# Master_MicroController.net
KiCad netlist of a schematic drawn in Altium Designer
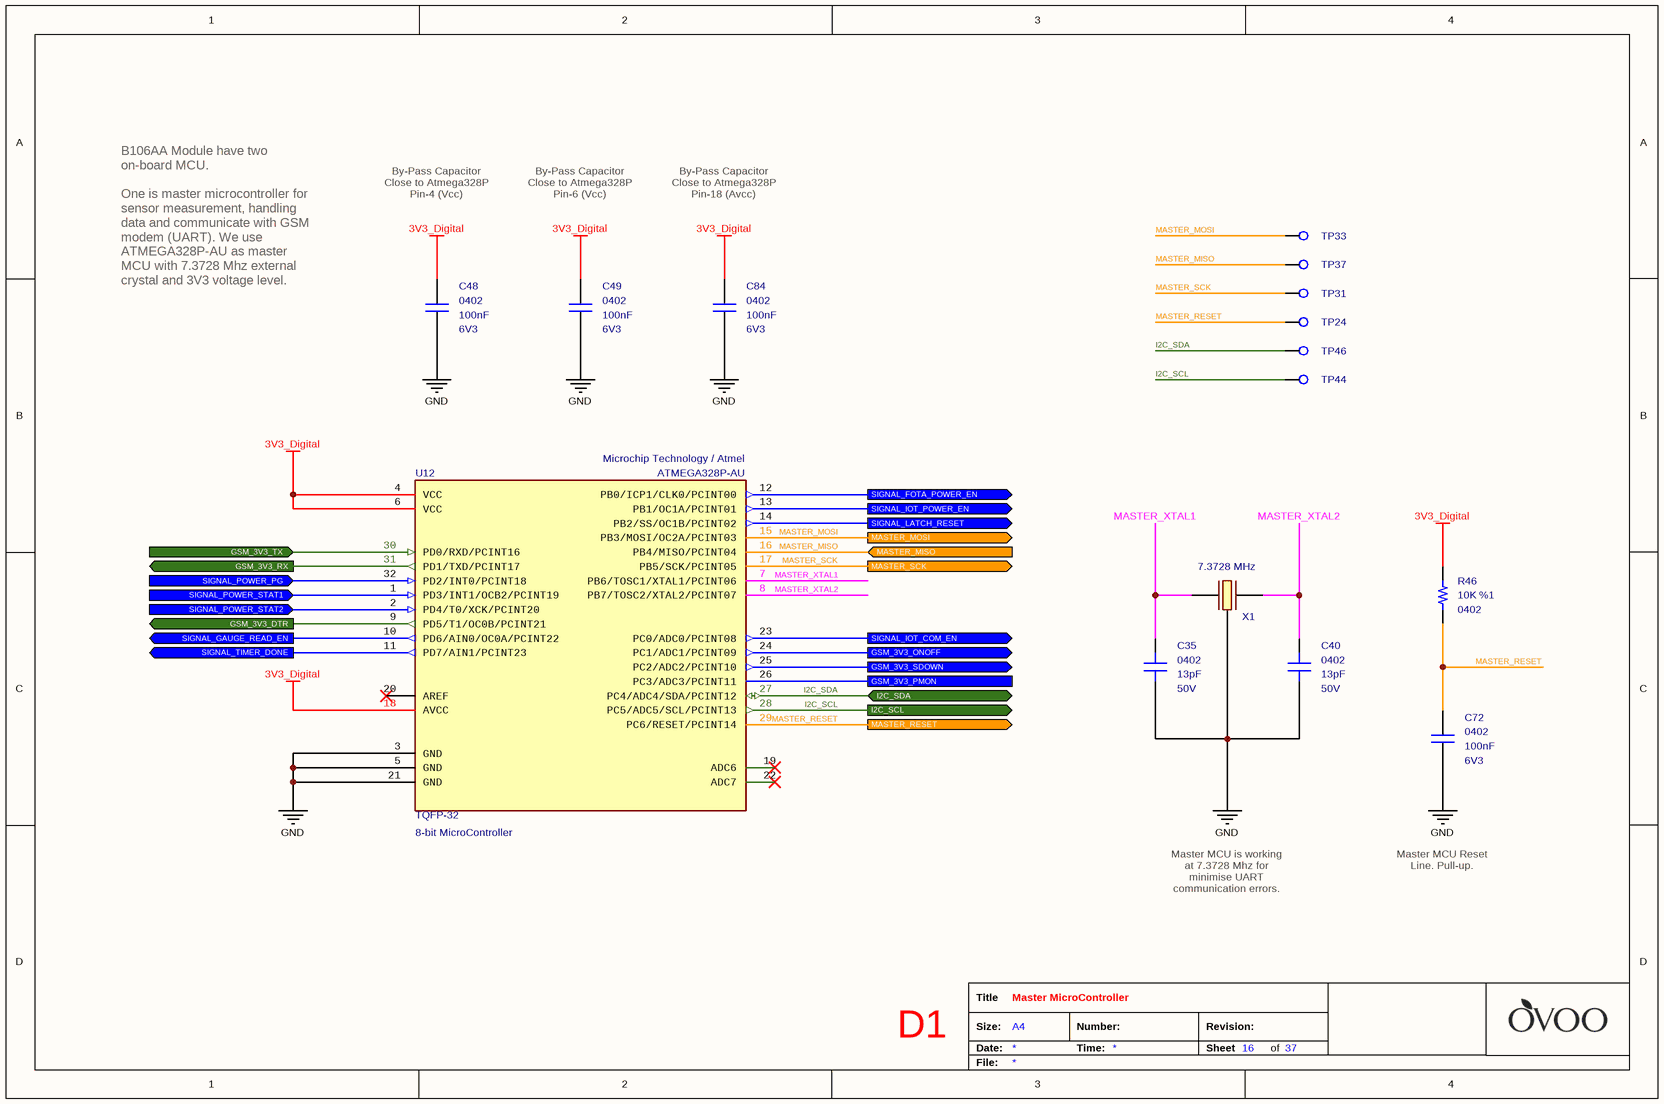
[diagram p0: Master MicroController.SchDoc]

(export (version "E")
  (design (tool "Eeschema 10.0.6"))
  (components
    (comp (ref "C35")
      (value "13pF")
      (footprint "CAPACITOR_0402")
      (description "Capacitor - 13pF [0402] (Ceramic)")
      (fields
        (field (name "MANUFACTURER_PART_NUMBER") "CBR04C130F5GAC")
        (field (name "MOUSER_PART_NUMBER") "80-CBR04C130F5GAC")
        (field (name "VOLTAGE") "50V")
        (field (name "CASE") "0402")
      )
      (libsource (lib "Ovoo_Schematic") (part "Capacitor - 13pF [0402-50V)"))
    )
    (comp (ref "C40")
      (value "13pF")
      (footprint "CAPACITOR_0402")
      (description "Capacitor - 13pF [0402] (Ceramic)")
      (fields
        (field (name "MANUFACTURER_PART_NUMBER") "CBR04C130F5GAC")
        (field (name "MOUSER_PART_NUMBER") "80-CBR04C130F5GAC")
        (field (name "VOLTAGE") "50V")
        (field (name "CASE") "0402")
      )
      (libsource (lib "Ovoo_Schematic") (part "Capacitor - 13pF [0402-50V)"))
    )
    (comp (ref "C48")
      (value "100nF")
      (footprint "CAPACITOR_0402")
      (description "Capacitor - 100nF [0402-6V3] (Ceramic)")
      (fields
        (field (name "MANUFACTURER_PART_NUMBER") "04026D104KAT4A")
        (field (name "MOUSER_PART_NUMBER") "581-04026D104KAT4A")
        (field (name "CASE") "0402")
        (field (name "VOLTAGE") "6V3")
      )
      (libsource (lib "Ovoo_Schematic") (part "Capacitor - 100nF [0402-6V3]"))
    )
    (comp (ref "C49")
      (value "100nF")
      (footprint "CAPACITOR_0402")
      (description "Capacitor - 100nF [0402-6V3] (Ceramic)")
      (fields
        (field (name "MANUFACTURER_PART_NUMBER") "04026D104KAT4A")
        (field (name "MOUSER_PART_NUMBER") "581-04026D104KAT4A")
        (field (name "CASE") "0402")
        (field (name "VOLTAGE") "6V3")
      )
      (libsource (lib "Ovoo_Schematic") (part "Capacitor - 100nF [0402-6V3]"))
    )
    (comp (ref "C72")
      (value "100nF")
      (footprint "CAPACITOR_0402")
      (description "Capacitor - 100nF [0402-6V3] (Ceramic)")
      (fields
        (field (name "MANUFACTURER_PART_NUMBER") "04026D104KAT4A")
        (field (name "MOUSER_PART_NUMBER") "581-04026D104KAT4A")
        (field (name "CASE") "0402")
        (field (name "VOLTAGE") "6V3")
      )
      (libsource (lib "Ovoo_Schematic") (part "Capacitor - 100nF [0402-6V3]"))
    )
    (comp (ref "C84")
      (value "100nF")
      (footprint "CAPACITOR_0402")
      (description "Capacitor - 100nF [0402-6V3] (Ceramic)")
      (fields
        (field (name "MANUFACTURER_PART_NUMBER") "04026D104KAT4A")
        (field (name "MOUSER_PART_NUMBER") "581-04026D104KAT4A")
        (field (name "CASE") "0402")
        (field (name "VOLTAGE") "6V3")
      )
      (libsource (lib "Ovoo_Schematic") (part "Capacitor - 100nF [0402-6V3]"))
    )
    (comp (ref "R46")
      (value "10K")
      (footprint "RESISTOR_0402")
      (description "Thick Film Resistors - SMD 1/16 W 10 Kohms 1%")
      (fields
        (field (name "MANUFACTURER_PART_NUMBER") "CRCW040210K0FKED")
        (field (name "MOUSER_PART_NUMBER") "71-CRCW0402-10K-E3")
        (field (name "TOLERANCE") "%1")
        (field (name "CASE") "0402")
      )
      (libsource (lib "Ovoo_Schematic") (part "Resistor - 10K"))
    )
    (comp (ref "TP24")
      (value "PCB - Test Point")
      (footprint "Test_Pad - Hole")
      (description "Test Point")
      (libsource (lib "Ovoo_Schematic") (part "PCB - Test Point"))
    )
    (comp (ref "TP31")
      (value "PCB - Test Point")
      (footprint "Test_Pad - Hole")
      (description "Test Point")
      (libsource (lib "Ovoo_Schematic") (part "PCB - Test Point"))
    )
    (comp (ref "TP33")
      (value "PCB - Test Point")
      (footprint "Test_Pad - Hole")
      (description "Test Point")
      (libsource (lib "Ovoo_Schematic") (part "PCB - Test Point"))
    )
    (comp (ref "TP37")
      (value "PCB - Test Point")
      (footprint "Test_Pad - Hole")
      (description "Test Point")
      (libsource (lib "Ovoo_Schematic") (part "PCB - Test Point"))
    )
    (comp (ref "TP44")
      (value "PCB - Test Point")
      (footprint "Test_Pad - Hole")
      (description "Test Point")
      (libsource (lib "Ovoo_Schematic") (part "PCB - Test Point"))
    )
    (comp (ref "TP46")
      (value "PCB - Test Point")
      (footprint "Test_Pad - Hole")
      (description "Test Point")
      (libsource (lib "Ovoo_Schematic") (part "PCB - Test Point"))
    )
    (comp (ref "U12")
      (value "8-bit MicroController")
      (footprint "TQFP32")
      (description "8-bit Microcontrollers - MCU 32KB In-system Flash 20MHz 1.8V-5.5V")
      (fields
        (field (name "MOUSER_PART_NUMBER") "556-ATMEGA328P-AU")
        (field (name "MANUFACTURER_PART_NUMBER") "ATMEGA328P-AU")
        (field (name "MANUFACTURER_NAME") "Microchip Technology / Atmel")
        (field (name "CASE") "TQFP-32")
      )
      (libsource (lib "Ovoo_Schematic") (part "IC - ATMEGA328P"))
    )
    (comp (ref "X1")
      (value "7.3728 MHz")
      (footprint "ABRACON_CRYSTAL")
      (description "Crystals 7.3728MHz 18pF -40C +85C")
      (fields
        (field (name "MANUFACTURER_PART_NUMBER") "ABMM2-7.3728MHZ-E2-T")
        (field (name "MOUSER_PART_NUMBER") "815-ABMM2-7.3-E2-T")
      )
      (libsource (lib "Ovoo_Schematic") (part "Crystal - 7.3728 MHz (Abracon)"))
    )
  )
  (nets
    (net (code "1") (name "/GSM_3V3_DTR") (class "Default")
      (node (ref "U12") (pin "9") (pinfunction "PD5/T1/OC0B/PCINT21_9") (pintype "output"))
    )
    (net (code "2") (name "/GSM_3V3_ONOFF") (class "Default")
      (node (ref "U12") (pin "24") (pinfunction "PC1/ADC1/PCINT09_24") (pintype "output"))
    )
    (net (code "3") (name "/GSM_3V3_PMON") (class "Default")
      (node (ref "U12") (pin "26") (pinfunction "PC3/ADC3/PCINT11_26") (pintype "passive"))
    )
    (net (code "4") (name "/GSM_3V3_RX") (class "Default")
      (node (ref "U12") (pin "31") (pinfunction "PD1/TXD/PCINT17_31") (pintype "output"))
    )
    (net (code "5") (name "/GSM_3V3_SDOWN") (class "Default")
      (node (ref "U12") (pin "25") (pinfunction "PC2/ADC2/PCINT10_25") (pintype "output"))
    )
    (net (code "6") (name "/GSM_3V3_TX") (class "Default")
      (node (ref "U12") (pin "30") (pinfunction "PD0/RXD/PCINT16_30") (pintype "input"))
    )
    (net (code "7") (name "/I2C_SCL") (class "Default")
      (node (ref "TP44") (pin "1") (pinfunction "1_1") (pintype "passive"))
      (node (ref "U12") (pin "28") (pinfunction "PC5/ADC5/SCL/PCINT13_28") (pintype "output"))
    )
    (net (code "8") (name "/I2C_SDA") (class "Default")
      (node (ref "TP46") (pin "1") (pinfunction "1_1") (pintype "passive"))
      (node (ref "U12") (pin "27") (pinfunction "PC4/ADC4/SDA/PCINT12_27") (pintype "bidirectional"))
    )
    (net (code "9") (name "/MASTER_MISO") (class "Default")
      (node (ref "TP37") (pin "1") (pinfunction "1_1") (pintype "passive"))
      (node (ref "U12") (pin "16") (pinfunction "PB4/MISO/PCINT04_16") (pintype "passive"))
    )
    (net (code "10") (name "/MASTER_MOSI") (class "Default")
      (node (ref "TP33") (pin "1") (pinfunction "1_1") (pintype "passive"))
      (node (ref "U12") (pin "15") (pinfunction "PB3/MOSI/OC2A/PCINT03_15") (pintype "passive"))
    )
    (net (code "11") (name "/MASTER_RESET") (class "Default")
      (node (ref "C72") (pin "2") (pinfunction "2_2") (pintype "passive"))
      (node (ref "R46") (pin "1") (pinfunction "1_1") (pintype "passive"))
      (node (ref "TP24") (pin "1") (pinfunction "1_1") (pintype "passive"))
      (node (ref "U12") (pin "29") (pinfunction "PC6/RESET/PCINT14_29") (pintype "passive"))
    )
    (net (code "12") (name "/MASTER_SCK") (class "Default")
      (node (ref "TP31") (pin "1") (pinfunction "1_1") (pintype "passive"))
      (node (ref "U12") (pin "17") (pinfunction "PB5/SCK/PCINT05_17") (pintype "passive"))
    )
    (net (code "13") (name "/MASTER_XTAL1") (class "Default")
      (node (ref "C35") (pin "2") (pinfunction "2_2") (pintype "passive"))
      (node (ref "U12") (pin "7") (pinfunction "PB6/TOSC1/XTAL1/PCINT06_7") (pintype "passive"))
      (node (ref "X1") (pin "3") (pinfunction "OUT/IN_3") (pintype "passive"))
    )
    (net (code "14") (name "/MASTER_XTAL2") (class "Default")
      (node (ref "C40") (pin "2") (pinfunction "2_2") (pintype "passive"))
      (node (ref "U12") (pin "8") (pinfunction "PB7/TOSC2/XTAL2/PCINT07_8") (pintype "passive"))
      (node (ref "X1") (pin "1") (pinfunction "IN/OUT_1") (pintype "passive"))
    )
    (net (code "15") (name "/SIGNAL_FOTA_POWER_EN") (class "Default")
      (node (ref "U12") (pin "12") (pinfunction "PB0/ICP1/CLK0/PCINT00_12") (pintype "output"))
    )
    (net (code "16") (name "/SIGNAL_GAUGE_READ_EN") (class "Default")
      (node (ref "U12") (pin "10") (pinfunction "PD6/AIN0/OC0A/PCINT22_10") (pintype "output"))
    )
    (net (code "17") (name "/SIGNAL_IOT_COM_EN") (class "Default")
      (node (ref "U12") (pin "23") (pinfunction "PC0/ADC0/PCINT08_23") (pintype "output"))
    )
    (net (code "18") (name "/SIGNAL_IOT_POWER_EN") (class "Default")
      (node (ref "U12") (pin "13") (pinfunction "PB1/OC1A/PCINT01_13") (pintype "output"))
    )
    (net (code "19") (name "/SIGNAL_LATCH_RESET") (class "Default")
      (node (ref "U12") (pin "14") (pinfunction "PB2/SS/OC1B/PCINT02_14") (pintype "output"))
    )
    (net (code "20") (name "/SIGNAL_POWER_PG") (class "Default")
      (node (ref "U12") (pin "32") (pinfunction "PD2/INT0/PCINT18_32") (pintype "input"))
    )
    (net (code "21") (name "/SIGNAL_POWER_STAT1") (class "Default")
      (node (ref "U12") (pin "1") (pinfunction "PD3/INT1/OCB2/PCINT19_1") (pintype "input"))
    )
    (net (code "22") (name "/SIGNAL_POWER_STAT2") (class "Default")
      (node (ref "U12") (pin "2") (pinfunction "PD4/T0/XCK/PCINT20_2") (pintype "input"))
    )
    (net (code "23") (name "/SIGNAL_TIMER_DONE") (class "Default")
      (node (ref "U12") (pin "11") (pinfunction "PD7/AIN1/PCINT23_11") (pintype "output"))
    )
    (net (code "24") (name "3V3_Digital") (class "Default")
      (node (ref "C48") (pin "2") (pinfunction "2_2") (pintype "passive"))
      (node (ref "C49") (pin "2") (pinfunction "2_2") (pintype "passive"))
      (node (ref "C84") (pin "2") (pinfunction "2_2") (pintype "passive"))
      (node (ref "R46") (pin "2") (pinfunction "2_2") (pintype "passive"))
      (node (ref "U12") (pin "18") (pinfunction "AVCC_18") (pintype "passive"))
      (node (ref "U12") (pin "4") (pinfunction "VCC_4") (pintype "power_in"))
      (node (ref "U12") (pin "6") (pinfunction "VCC_6") (pintype "power_in"))
    )
    (net (code "25") (name "GND") (class "Default")
      (node (ref "C35") (pin "1") (pinfunction "1_1") (pintype "passive"))
      (node (ref "C40") (pin "1") (pinfunction "1_1") (pintype "passive"))
      (node (ref "C48") (pin "1") (pinfunction "1_1") (pintype "passive"))
      (node (ref "C49") (pin "1") (pinfunction "1_1") (pintype "passive"))
      (node (ref "C72") (pin "1") (pinfunction "1_1") (pintype "passive"))
      (node (ref "C84") (pin "1") (pinfunction "1_1") (pintype "passive"))
      (node (ref "U12") (pin "21") (pinfunction "GND_21") (pintype "power_in"))
      (node (ref "U12") (pin "3") (pinfunction "GND_3") (pintype "power_in"))
      (node (ref "U12") (pin "5") (pinfunction "GND_5") (pintype "power_in"))
      (node (ref "X1") (pin "2") (pinfunction "GND_2") (pintype "passive"))
    )
    (net (code "26") (name "unconnected-(U12-ADC6-Pad19)") (class "Default")
      (node (ref "U12") (pin "19") (pinfunction "ADC6_19") (pintype "passive+no_connect"))
    )
    (net (code "27") (name "unconnected-(U12-ADC7-Pad22)") (class "Default")
      (node (ref "U12") (pin "22") (pinfunction "ADC7_22") (pintype "passive+no_connect"))
    )
    (net (code "28") (name "unconnected-(U12-AREF-Pad20)") (class "Default")
      (node (ref "U12") (pin "20") (pinfunction "AREF_20") (pintype "passive+no_connect"))
    )
    (net (code "29") (name "unconnected-(X1-GND-Pad4)") (class "Default")
      (node (ref "X1") (pin "4") (pinfunction "GND_4") (pintype "passive"))
    )
  )
)
